# ECE445-Transmitter-Schematic.net
KiCad netlist of a schematic drawn in EAGLE
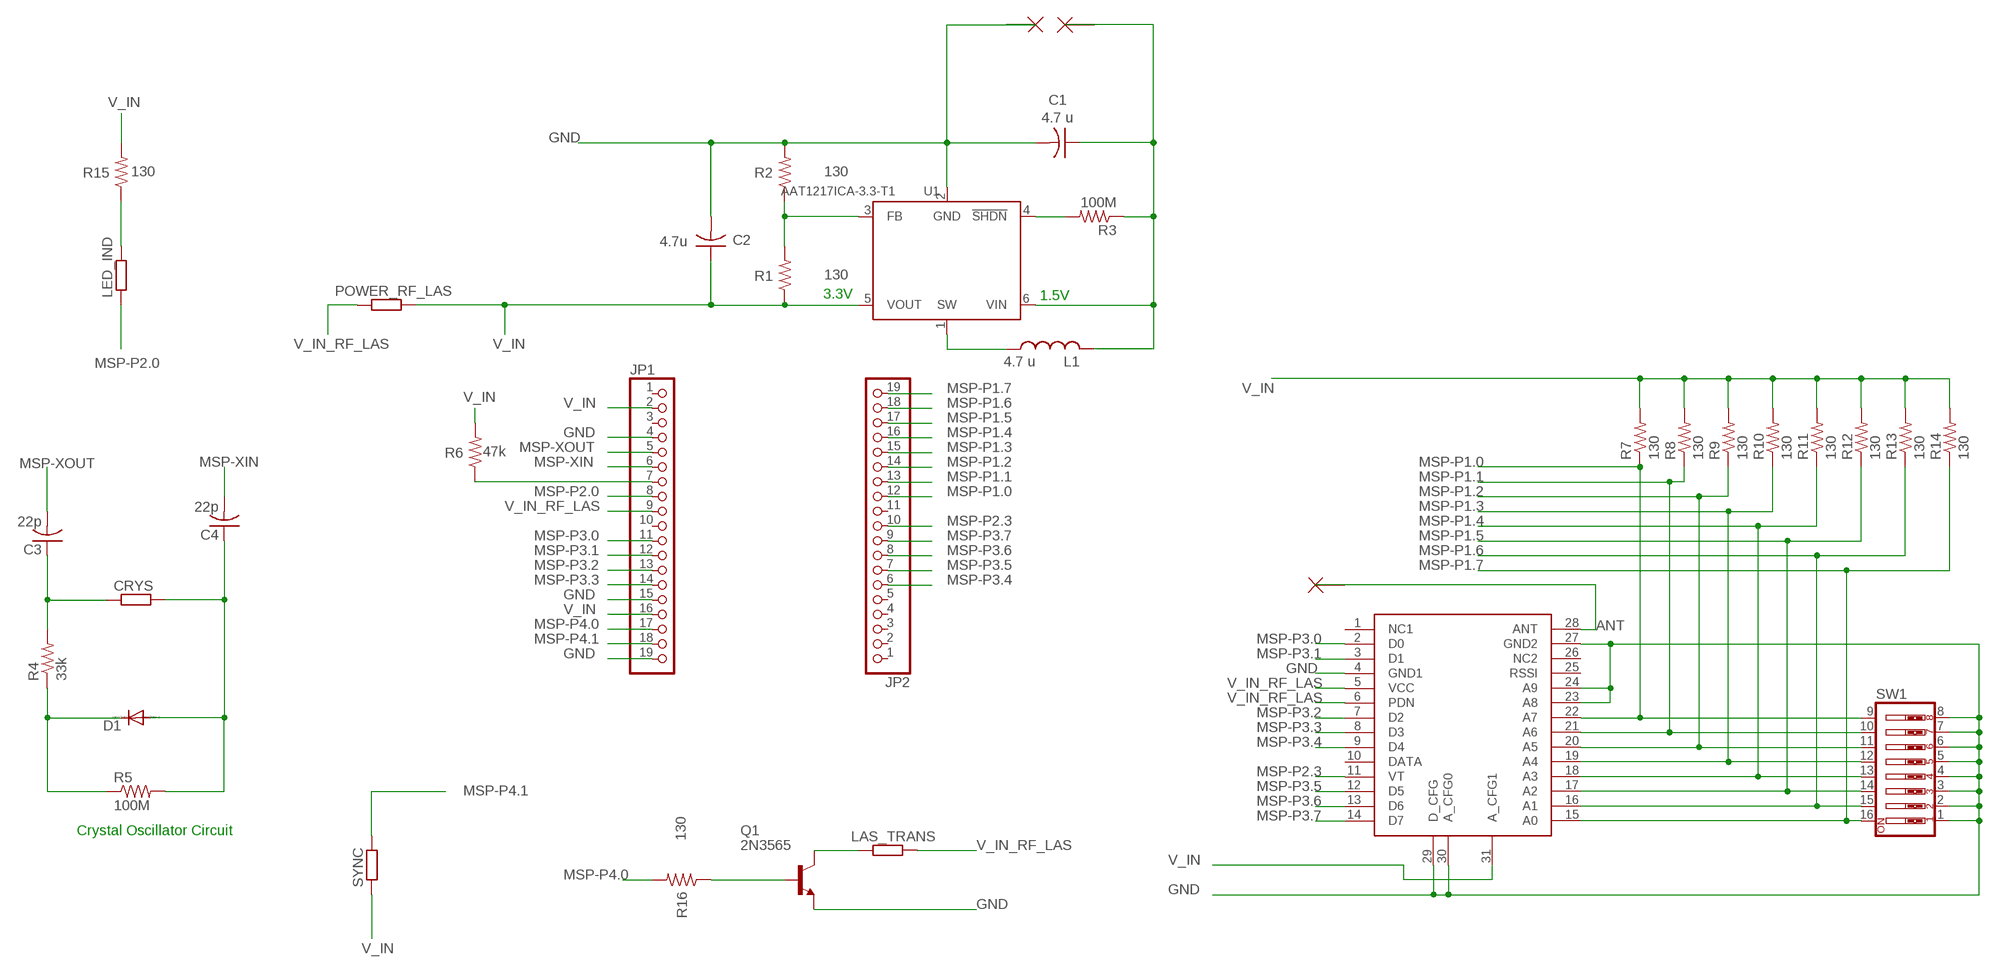
[diagram p0: schematic, sheet 1]

(export (version "E")
  (design (tool "Eeschema 10.0.6"))
  (components
    (comp (ref "C1")
      (value "4.7 u")
      (footprint "eagle-import:C025-024X044")
      (libsource (lib "eagle-import") (part "C-US025-024X044"))
    )
    (comp (ref "C2")
      (value "4.7u")
      (footprint "eagle-import:C025-024X044")
      (libsource (lib "eagle-import") (part "C-US025-024X044"))
    )
    (comp (ref "C3")
      (value "22p")
      (footprint "eagle-import:C025-024X044")
      (libsource (lib "eagle-import") (part "C-US025-024X044"))
    )
    (comp (ref "C4")
      (value "22p")
      (footprint "eagle-import:C025-024X044")
      (libsource (lib "eagle-import") (part "C-US025-024X044"))
    )
    (comp (ref "CRYS")
      (value "R-EU_0204/5")
      (footprint "eagle-import:0204_5")
      (libsource (lib "eagle-import") (part "R-EU_0204/5"))
    )
    (comp (ref "D1")
      (value "1N4004")
      (footprint "eagle-import:DO41-10")
      (libsource (lib "eagle-import") (part "1N4004"))
    )
    (comp (ref "JP1")
      (value "PINHD-1X19")
      (footprint "eagle-import:1X19")
      (libsource (lib "eagle-import") (part "PINHD-1X19"))
    )
    (comp (ref "JP2")
      (value "PINHD-1X19")
      (footprint "eagle-import:1X19")
      (libsource (lib "eagle-import") (part "PINHD-1X19"))
    )
    (comp (ref "L1")
      (value "4.7 u")
      (footprint "eagle-import:0204_5")
      (libsource (lib "eagle-import") (part "L-US0204/5"))
    )
    (comp (ref "LAS_TRANS")
      (value "R-EU_0204/5")
      (footprint "eagle-import:0204_5")
      (libsource (lib "eagle-import") (part "R-EU_0204/5"))
    )
    (comp (ref "LED_IND")
      (value "R-EU_0204/5")
      (footprint "eagle-import:0204_5")
      (libsource (lib "eagle-import") (part "R-EU_0204/5"))
    )
    (comp (ref "POWER_RF_LAS")
      (value "R-EU_0204/5")
      (footprint "eagle-import:0204_5")
      (libsource (lib "eagle-import") (part "R-EU_0204/5"))
    )
    (comp (ref "Q1")
      (value "2N3565")
      (footprint "eagle-import:TO92")
      (libsource (lib "eagle-import") (part "2N3565"))
    )
    (comp (ref "R1")
      (value "130")
      (footprint "eagle-import:0204_5")
      (libsource (lib "eagle-import") (part "R-US_0204/5"))
    )
    (comp (ref "R2")
      (value "130")
      (footprint "eagle-import:0204_5")
      (libsource (lib "eagle-import") (part "R-US_0204/5"))
    )
    (comp (ref "R3")
      (value "100M")
      (footprint "eagle-import:0204V")
      (libsource (lib "eagle-import") (part "R-US_0204/2V"))
    )
    (comp (ref "R4")
      (value "33k")
      (footprint "eagle-import:0204V")
      (libsource (lib "eagle-import") (part "R-US_0204/2V"))
    )
    (comp (ref "R5")
      (value "100M")
      (footprint "eagle-import:0204V")
      (libsource (lib "eagle-import") (part "R-US_0204/2V"))
    )
    (comp (ref "R6")
      (value "47k")
      (footprint "eagle-import:0204_5")
      (libsource (lib "eagle-import") (part "R-US_0204/5"))
    )
    (comp (ref "R7")
      (value "130")
      (footprint "eagle-import:0204_5")
      (libsource (lib "eagle-import") (part "R-US_0204/5"))
    )
    (comp (ref "R8")
      (value "130")
      (footprint "eagle-import:0204_5")
      (libsource (lib "eagle-import") (part "R-US_0204/5"))
    )
    (comp (ref "R9")
      (value "130")
      (footprint "eagle-import:0204_5")
      (libsource (lib "eagle-import") (part "R-US_0204/5"))
    )
    (comp (ref "R10")
      (value "130")
      (footprint "eagle-import:0204_5")
      (libsource (lib "eagle-import") (part "R-US_0204/5"))
    )
    (comp (ref "R11")
      (value "130")
      (footprint "eagle-import:0204_5")
      (libsource (lib "eagle-import") (part "R-US_0204/5"))
    )
    (comp (ref "R12")
      (value "130")
      (footprint "eagle-import:0204_5")
      (libsource (lib "eagle-import") (part "R-US_0204/5"))
    )
    (comp (ref "R13")
      (value "130")
      (footprint "eagle-import:0204_5")
      (libsource (lib "eagle-import") (part "R-US_0204/5"))
    )
    (comp (ref "R14")
      (value "130")
      (footprint "eagle-import:0204_5")
      (libsource (lib "eagle-import") (part "R-US_0204/5"))
    )
    (comp (ref "R15")
      (value "130")
      (footprint "eagle-import:0204_5")
      (libsource (lib "eagle-import") (part "R-US_0204/5"))
    )
    (comp (ref "R16")
      (value "130")
      (footprint "eagle-import:0204_5")
      (libsource (lib "eagle-import") (part "R-US_0204/5"))
    )
    (comp (ref "SW1")
      (value "SW_DIP-8")
      (footprint "eagle-import:EDG-08")
      (libsource (lib "eagle-import") (part "SW_DIP-8"))
    )
    (comp (ref "SYNC")
      (value "R-EU_0204/5")
      (footprint "eagle-import:0204_5")
      (libsource (lib "eagle-import") (part "R-EU_0204/5"))
    )
    (comp (ref "U$1")
      (value "KH3-RXM-LINX-315")
      (footprint "eagle-import:KH3-RXM-LINX-315")
      (libsource (lib "eagle-import") (part "KH3-RXM-LINX-315"))
    )
    (comp (ref "U$2")
      (value "NO_CONNECT")
      (footprint "eagle-import:NO_CONNECT")
      (libsource (lib "eagle-import") (part "NO_CONNECT"))
    )
    (comp (ref "U$3")
      (value "NO_CONNECT")
      (footprint "eagle-import:NO_CONNECT")
      (libsource (lib "eagle-import") (part "NO_CONNECT"))
    )
    (comp (ref "U$4")
      (value "NO_CONNECT")
      (footprint "eagle-import:NO_CONNECT")
      (libsource (lib "eagle-import") (part "NO_CONNECT"))
    )
    (comp (ref "U1")
      (value "AAT1217ICA-3.3-T1")
      (footprint "eagle-import:TSOT-23-6")
      (libsource (lib "eagle-import") (part "AAT1217ICA-3.3-T1"))
    )
  )
  (nets
    (net (code "1") (name "/ANT") (class "Default")
      (node (ref "U$1") (pin "28") (pinfunction "ANT_28") (pintype "bidirectional"))
      (node (ref "U$4") (pin "P$1") (pinfunction "NC_P$1") (pintype "bidirectional"))
    )
    (net (code "2") (name "/GND") (class "Default")
      (node (ref "C1") (pin "2") (pinfunction "2_2") (pintype "passive"))
      (node (ref "C2") (pin "2") (pinfunction "2_2") (pintype "passive"))
      (node (ref "JP1") (pin "15") (pinfunction "15_15") (pintype "passive"))
      (node (ref "JP1") (pin "19") (pinfunction "19_19") (pintype "passive"))
      (node (ref "JP1") (pin "4") (pinfunction "4_4") (pintype "passive"))
      (node (ref "Q1") (pin "3") (pinfunction "E_3") (pintype "passive"))
      (node (ref "R2") (pin "2") (pinfunction "2_2") (pintype "passive"))
      (node (ref "SW1") (pin "1") (pinfunction "1_1") (pintype "passive"))
      (node (ref "SW1") (pin "2") (pinfunction "2_2") (pintype "passive"))
      (node (ref "SW1") (pin "3") (pinfunction "3_3") (pintype "passive"))
      (node (ref "SW1") (pin "4") (pinfunction "4_4") (pintype "passive"))
      (node (ref "SW1") (pin "5") (pinfunction "5_5") (pintype "passive"))
      (node (ref "SW1") (pin "6") (pinfunction "6_6") (pintype "passive"))
      (node (ref "SW1") (pin "7") (pinfunction "7_7") (pintype "passive"))
      (node (ref "SW1") (pin "8") (pinfunction "8_8") (pintype "passive"))
      (node (ref "U$1") (pin "23") (pinfunction "A8_23") (pintype "bidirectional"))
      (node (ref "U$1") (pin "24") (pinfunction "A9_24") (pintype "bidirectional"))
      (node (ref "U$1") (pin "27") (pinfunction "GND2_27") (pintype "bidirectional"))
      (node (ref "U$1") (pin "29") (pinfunction "D_CFG_29") (pintype "bidirectional"))
      (node (ref "U$1") (pin "30") (pinfunction "A_CFG0_30") (pintype "bidirectional"))
      (node (ref "U$1") (pin "4") (pinfunction "GND1_4") (pintype "bidirectional"))
      (node (ref "U$2") (pin "P$1") (pinfunction "NC_P$1") (pintype "bidirectional"))
      (node (ref "U1") (pin "2") (pinfunction "GND_2") (pintype "bidirectional"))
    )
    (net (code "3") (name "/MSP-P1.0") (class "Default")
      (node (ref "JP2") (pin "12") (pinfunction "12_12") (pintype "passive"))
      (node (ref "R7") (pin "1") (pinfunction "1_1") (pintype "passive"))
      (node (ref "SW1") (pin "9") (pinfunction "9_9") (pintype "passive"))
      (node (ref "U$1") (pin "22") (pinfunction "A7_22") (pintype "bidirectional"))
    )
    (net (code "4") (name "/MSP-P1.1") (class "Default")
      (node (ref "JP2") (pin "13") (pinfunction "13_13") (pintype "passive"))
      (node (ref "R8") (pin "1") (pinfunction "1_1") (pintype "passive"))
      (node (ref "SW1") (pin "10") (pinfunction "10_10") (pintype "passive"))
      (node (ref "U$1") (pin "21") (pinfunction "A6_21") (pintype "bidirectional"))
    )
    (net (code "5") (name "/MSP-P1.2") (class "Default")
      (node (ref "JP2") (pin "14") (pinfunction "14_14") (pintype "passive"))
      (node (ref "R9") (pin "1") (pinfunction "1_1") (pintype "passive"))
      (node (ref "SW1") (pin "11") (pinfunction "11_11") (pintype "passive"))
      (node (ref "U$1") (pin "20") (pinfunction "A5_20") (pintype "bidirectional"))
    )
    (net (code "6") (name "/MSP-P1.3") (class "Default")
      (node (ref "JP2") (pin "15") (pinfunction "15_15") (pintype "passive"))
      (node (ref "R10") (pin "1") (pinfunction "1_1") (pintype "passive"))
      (node (ref "SW1") (pin "12") (pinfunction "12_12") (pintype "passive"))
      (node (ref "U$1") (pin "19") (pinfunction "A4_19") (pintype "bidirectional"))
    )
    (net (code "7") (name "/MSP-P1.4") (class "Default")
      (node (ref "JP2") (pin "16") (pinfunction "16_16") (pintype "passive"))
      (node (ref "R11") (pin "1") (pinfunction "1_1") (pintype "passive"))
      (node (ref "SW1") (pin "13") (pinfunction "13_13") (pintype "passive"))
      (node (ref "U$1") (pin "18") (pinfunction "A3_18") (pintype "bidirectional"))
    )
    (net (code "8") (name "/MSP-P1.5") (class "Default")
      (node (ref "JP2") (pin "17") (pinfunction "17_17") (pintype "passive"))
      (node (ref "R12") (pin "1") (pinfunction "1_1") (pintype "passive"))
      (node (ref "SW1") (pin "14") (pinfunction "14_14") (pintype "passive"))
      (node (ref "U$1") (pin "17") (pinfunction "A2_17") (pintype "bidirectional"))
    )
    (net (code "9") (name "/MSP-P1.6") (class "Default")
      (node (ref "JP2") (pin "18") (pinfunction "18_18") (pintype "passive"))
      (node (ref "R13") (pin "1") (pinfunction "1_1") (pintype "passive"))
      (node (ref "SW1") (pin "15") (pinfunction "15_15") (pintype "passive"))
      (node (ref "U$1") (pin "16") (pinfunction "A1_16") (pintype "bidirectional"))
    )
    (net (code "10") (name "/MSP-P1.7") (class "Default")
      (node (ref "JP2") (pin "19") (pinfunction "19_19") (pintype "passive"))
      (node (ref "R14") (pin "1") (pinfunction "1_1") (pintype "passive"))
      (node (ref "SW1") (pin "16") (pinfunction "16_16") (pintype "passive"))
      (node (ref "U$1") (pin "15") (pinfunction "A0_15") (pintype "bidirectional"))
    )
    (net (code "11") (name "/MSP-P2.0") (class "Default")
      (node (ref "JP1") (pin "8") (pinfunction "8_8") (pintype "passive"))
      (node (ref "LED_IND") (pin "1") (pinfunction "1_1") (pintype "passive"))
    )
    (net (code "12") (name "/MSP-P2.3") (class "Default")
      (node (ref "JP2") (pin "10") (pinfunction "10_10") (pintype "passive"))
      (node (ref "U$1") (pin "11") (pinfunction "VT_11") (pintype "bidirectional"))
    )
    (net (code "13") (name "/MSP-P3.0") (class "Default")
      (node (ref "JP1") (pin "11") (pinfunction "11_11") (pintype "passive"))
      (node (ref "U$1") (pin "2") (pinfunction "D0_2") (pintype "bidirectional"))
    )
    (net (code "14") (name "/MSP-P3.1") (class "Default")
      (node (ref "JP1") (pin "12") (pinfunction "12_12") (pintype "passive"))
      (node (ref "U$1") (pin "3") (pinfunction "D1_3") (pintype "bidirectional"))
    )
    (net (code "15") (name "/MSP-P3.2") (class "Default")
      (node (ref "JP1") (pin "13") (pinfunction "13_13") (pintype "passive"))
      (node (ref "U$1") (pin "7") (pinfunction "D2_7") (pintype "bidirectional"))
    )
    (net (code "16") (name "/MSP-P3.3") (class "Default")
      (node (ref "JP1") (pin "14") (pinfunction "14_14") (pintype "passive"))
      (node (ref "U$1") (pin "8") (pinfunction "D3_8") (pintype "bidirectional"))
    )
    (net (code "17") (name "/MSP-P3.4") (class "Default")
      (node (ref "JP2") (pin "6") (pinfunction "6_6") (pintype "passive"))
      (node (ref "U$1") (pin "9") (pinfunction "D4_9") (pintype "bidirectional"))
    )
    (net (code "18") (name "/MSP-P3.5") (class "Default")
      (node (ref "JP2") (pin "7") (pinfunction "7_7") (pintype "passive"))
      (node (ref "U$1") (pin "12") (pinfunction "D5_12") (pintype "bidirectional"))
    )
    (net (code "19") (name "/MSP-P3.6") (class "Default")
      (node (ref "JP2") (pin "8") (pinfunction "8_8") (pintype "passive"))
      (node (ref "U$1") (pin "13") (pinfunction "D6_13") (pintype "bidirectional"))
    )
    (net (code "20") (name "/MSP-P3.7") (class "Default")
      (node (ref "JP2") (pin "9") (pinfunction "9_9") (pintype "passive"))
      (node (ref "U$1") (pin "14") (pinfunction "D7_14") (pintype "bidirectional"))
    )
    (net (code "21") (name "/MSP-P4.0") (class "Default")
      (node (ref "JP1") (pin "17") (pinfunction "17_17") (pintype "passive"))
      (node (ref "R16") (pin "2") (pinfunction "2_2") (pintype "passive"))
    )
    (net (code "22") (name "/MSP-P4.1") (class "Default")
      (node (ref "JP1") (pin "18") (pinfunction "18_18") (pintype "passive"))
      (node (ref "SYNC") (pin "2") (pinfunction "2_2") (pintype "passive"))
    )
    (net (code "23") (name "/MSP-XIN") (class "Default")
      (node (ref "C4") (pin "2") (pinfunction "2_2") (pintype "passive"))
      (node (ref "JP1") (pin "6") (pinfunction "6_6") (pintype "passive"))
    )
    (net (code "24") (name "/MSP-XOUT") (class "Default")
      (node (ref "C3") (pin "2") (pinfunction "2_2") (pintype "passive"))
      (node (ref "JP1") (pin "5") (pinfunction "5_5") (pintype "passive"))
    )
    (net (code "25") (name "/V_IN") (class "Default")
      (node (ref "C2") (pin "1") (pinfunction "1_1") (pintype "passive"))
      (node (ref "JP1") (pin "16") (pinfunction "16_16") (pintype "passive"))
      (node (ref "JP1") (pin "2") (pinfunction "2_2") (pintype "passive"))
      (node (ref "POWER_RF_LAS") (pin "2") (pinfunction "2_2") (pintype "passive"))
      (node (ref "R1") (pin "1") (pinfunction "1_1") (pintype "passive"))
      (node (ref "R10") (pin "2") (pinfunction "2_2") (pintype "passive"))
      (node (ref "R11") (pin "2") (pinfunction "2_2") (pintype "passive"))
      (node (ref "R12") (pin "2") (pinfunction "2_2") (pintype "passive"))
      (node (ref "R13") (pin "2") (pinfunction "2_2") (pintype "passive"))
      (node (ref "R14") (pin "2") (pinfunction "2_2") (pintype "passive"))
      (node (ref "R15") (pin "2") (pinfunction "2_2") (pintype "passive"))
      (node (ref "R6") (pin "2") (pinfunction "2_2") (pintype "passive"))
      (node (ref "R7") (pin "2") (pinfunction "2_2") (pintype "passive"))
      (node (ref "R8") (pin "2") (pinfunction "2_2") (pintype "passive"))
      (node (ref "R9") (pin "2") (pinfunction "2_2") (pintype "passive"))
      (node (ref "SYNC") (pin "1") (pinfunction "1_1") (pintype "passive"))
      (node (ref "U$1") (pin "31") (pinfunction "A_CFG1_31") (pintype "bidirectional"))
      (node (ref "U1") (pin "5") (pinfunction "VOUT_5") (pintype "bidirectional"))
    )
    (net (code "26") (name "/V_IN_RF_LAS") (class "Default")
      (node (ref "JP1") (pin "9") (pinfunction "9_9") (pintype "passive"))
      (node (ref "LAS_TRANS") (pin "2") (pinfunction "2_2") (pintype "passive"))
      (node (ref "POWER_RF_LAS") (pin "1") (pinfunction "1_1") (pintype "passive"))
      (node (ref "U$1") (pin "5") (pinfunction "VCC_5") (pintype "bidirectional"))
      (node (ref "U$1") (pin "6") (pinfunction "PDN_6") (pintype "bidirectional"))
    )
    (net (code "27") (name "Net-(C3-Pad1)") (class "Default")
      (node (ref "C3") (pin "1") (pinfunction "1_1") (pintype "passive"))
      (node (ref "CRYS") (pin "1") (pinfunction "1_1") (pintype "passive"))
      (node (ref "R4") (pin "2") (pinfunction "2_2") (pintype "passive"))
    )
    (net (code "28") (name "Net-(C4-Pad1)") (class "Default")
      (node (ref "C4") (pin "1") (pinfunction "1_1") (pintype "passive"))
      (node (ref "CRYS") (pin "2") (pinfunction "2_2") (pintype "passive"))
      (node (ref "D1") (pin "A") (pinfunction "A_A") (pintype "passive"))
      (node (ref "R5") (pin "2") (pinfunction "2_2") (pintype "passive"))
    )
    (net (code "29") (name "Net-(D1-PadC)") (class "Default")
      (node (ref "D1") (pin "C") (pinfunction "C_C") (pintype "passive"))
      (node (ref "R4") (pin "1") (pinfunction "1_1") (pintype "passive"))
      (node (ref "R5") (pin "1") (pinfunction "1_1") (pintype "passive"))
    )
    (net (code "30") (name "Net-(JP1-Pad7)") (class "Default")
      (node (ref "JP1") (pin "7") (pinfunction "7_7") (pintype "passive"))
      (node (ref "R6") (pin "1") (pinfunction "1_1") (pintype "passive"))
    )
    (net (code "31") (name "Net-(LED_IND-Pad2)") (class "Default")
      (node (ref "LED_IND") (pin "2") (pinfunction "2_2") (pintype "passive"))
      (node (ref "R15") (pin "1") (pinfunction "1_1") (pintype "passive"))
    )
    (net (code "32") (name "Net-(Q1-B)") (class "Default")
      (node (ref "Q1") (pin "2") (pinfunction "B_2") (pintype "passive"))
      (node (ref "R16") (pin "1") (pinfunction "1_1") (pintype "passive"))
    )
    (net (code "33") (name "Net-(Q1-C)") (class "Default")
      (node (ref "LAS_TRANS") (pin "1") (pinfunction "1_1") (pintype "passive"))
      (node (ref "Q1") (pin "1") (pinfunction "C_1") (pintype "passive"))
    )
    (net (code "34") (name "Net-(U$3-NC)") (class "Default")
      (node (ref "C1") (pin "1") (pinfunction "1_1") (pintype "passive"))
      (node (ref "L1") (pin "2") (pinfunction "2_2") (pintype "passive"))
      (node (ref "R3") (pin "1") (pinfunction "1_1") (pintype "passive"))
      (node (ref "U$3") (pin "P$1") (pinfunction "NC_P$1") (pintype "bidirectional"))
      (node (ref "U1") (pin "6") (pinfunction "VIN_6") (pintype "bidirectional"))
    )
    (net (code "35") (name "Net-(U1-FB)") (class "Default")
      (node (ref "R1") (pin "2") (pinfunction "2_2") (pintype "passive"))
      (node (ref "R2") (pin "1") (pinfunction "1_1") (pintype "passive"))
      (node (ref "U1") (pin "3") (pinfunction "FB_3") (pintype "bidirectional"))
    )
    (net (code "36") (name "Net-(U1-SW)") (class "Default")
      (node (ref "L1") (pin "1") (pinfunction "1_1") (pintype "passive"))
      (node (ref "U1") (pin "1") (pinfunction "SW_1") (pintype "bidirectional"))
    )
    (net (code "37") (name "Net-(U1-~{SHDN})") (class "Default")
      (node (ref "R3") (pin "2") (pinfunction "2_2") (pintype "passive"))
      (node (ref "U1") (pin "4") (pinfunction "~{SHDN}_4") (pintype "bidirectional"))
    )
    (net (code "38") (name "unconnected-(JP1-Pad1)") (class "Default")
      (node (ref "JP1") (pin "1") (pinfunction "1_1") (pintype "passive"))
    )
    (net (code "39") (name "unconnected-(JP1-Pad3)") (class "Default")
      (node (ref "JP1") (pin "3") (pinfunction "3_3") (pintype "passive"))
    )
    (net (code "40") (name "unconnected-(JP1-Pad10)") (class "Default")
      (node (ref "JP1") (pin "10") (pinfunction "10_10") (pintype "passive"))
    )
    (net (code "41") (name "unconnected-(JP2-Pad1)") (class "Default")
      (node (ref "JP2") (pin "1") (pinfunction "1_1") (pintype "passive"))
    )
    (net (code "42") (name "unconnected-(JP2-Pad2)") (class "Default")
      (node (ref "JP2") (pin "2") (pinfunction "2_2") (pintype "passive"))
    )
    (net (code "43") (name "unconnected-(JP2-Pad3)") (class "Default")
      (node (ref "JP2") (pin "3") (pinfunction "3_3") (pintype "passive"))
    )
    (net (code "44") (name "unconnected-(JP2-Pad4)") (class "Default")
      (node (ref "JP2") (pin "4") (pinfunction "4_4") (pintype "passive"))
    )
    (net (code "45") (name "unconnected-(JP2-Pad5)") (class "Default")
      (node (ref "JP2") (pin "5") (pinfunction "5_5") (pintype "passive"))
    )
    (net (code "46") (name "unconnected-(JP2-Pad11)") (class "Default")
      (node (ref "JP2") (pin "11") (pinfunction "11_11") (pintype "passive"))
    )
    (net (code "47") (name "unconnected-(U$1-DATA-Pad10)") (class "Default")
      (node (ref "U$1") (pin "10") (pinfunction "DATA_10") (pintype "bidirectional"))
    )
    (net (code "48") (name "unconnected-(U$1-NC1-Pad1)") (class "Default")
      (node (ref "U$1") (pin "1") (pinfunction "NC1_1") (pintype "no_connect"))
    )
    (net (code "49") (name "unconnected-(U$1-NC2-Pad26)") (class "Default")
      (node (ref "U$1") (pin "26") (pinfunction "NC2_26") (pintype "no_connect"))
    )
    (net (code "50") (name "unconnected-(U$1-RSSI-Pad25)") (class "Default")
      (node (ref "U$1") (pin "25") (pinfunction "RSSI_25") (pintype "bidirectional"))
    )
  )
)
